# ADCHighVoltageInputsSchDoc.net
KiCad netlist of a schematic drawn in Altium Designer
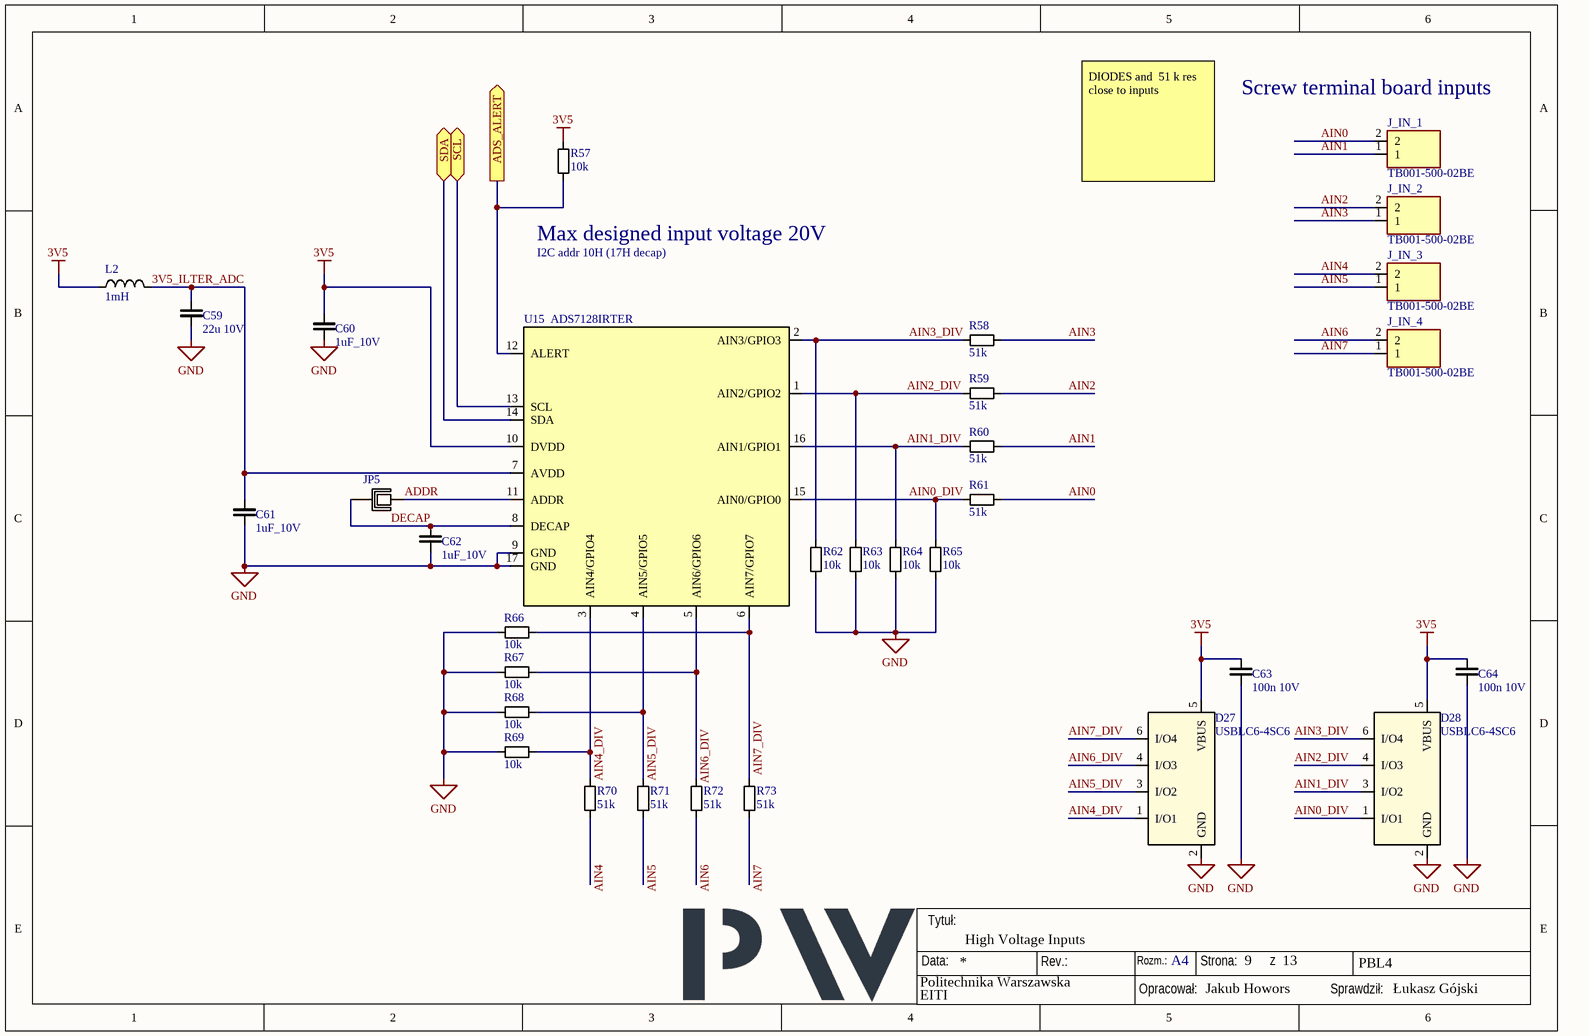
[diagram p0: ADCHighVoltageInputsSchDoc.SchDoc]

(export (version "E")
  (design (tool "Eeschema 10.0.6"))
  (components
    (comp (ref "C59")
      (value "22u 10V")
      (footprint "C_1206")
      (description "Ceramic capacitor")
      (fields (field (name "VOLTAGE") "10V") (field (name "TOLERANCE") "20%"))
      (libsource (lib "Common") (part "C_22uF_10V"))
    )
    (comp (ref "C60")
      (value "1uF_10V")
      (footprint "C_0603")
      (description "Ceramic capacitor")
      (fields (field (name "VOLTAGE") "10V") (field (name "TOLERANCE") "10%"))
      (libsource (lib "Common") (part "C_1uF_10V"))
    )
    (comp (ref "C61")
      (value "1uF_10V")
      (footprint "C_0603")
      (description "Ceramic capacitor")
      (fields (field (name "VOLTAGE") "10V") (field (name "TOLERANCE") "10%"))
      (libsource (lib "Common") (part "C_1uF_10V"))
    )
    (comp (ref "C62")
      (value "1uF_10V")
      (footprint "C_0603")
      (description "Ceramic capacitor")
      (fields (field (name "VOLTAGE") "10V") (field (name "TOLERANCE") "10%"))
      (libsource (lib "Common") (part "C_1uF_10V"))
    )
    (comp (ref "C63")
      (value "100n 10V")
      (footprint "C_0603")
      (description "Ceramic capacitor")
      (fields (field (name "VOLTAGE") "10V") (field (name "TOLERANCE") "10%"))
      (libsource (lib "Common") (part "C_100nF_10V"))
    )
    (comp (ref "C64")
      (value "100n 10V")
      (footprint "C_0603")
      (description "Ceramic capacitor")
      (fields (field (name "VOLTAGE") "10V") (field (name "TOLERANCE") "10%"))
      (libsource (lib "Common") (part "C_100nF_10V"))
    )
    (comp (ref "D27")
      (value "USBLC6-4SC6")
      (footprint "SOT23-6L_STM")
      (description "Very low capacitance ESD protection")
      (fields (field (name "MANUFACTURER") "STMicroelectronics"))
      (libsource (lib "Common") (part "USBLC6-4SC6"))
    )
    (comp (ref "D28")
      (value "USBLC6-4SC6")
      (footprint "SOT23-6L_STM")
      (description "Very low capacitance ESD protection")
      (fields (field (name "MANUFACTURER") "STMicroelectronics"))
      (libsource (lib "Common") (part "USBLC6-4SC6"))
    )
    (comp (ref "JP5")
      (value "JUMPER")
      (footprint "Jumper")
      (description "Jumper on traces")
      (libsource (lib "Common") (part "Jumper x2"))
    )
    (comp (ref "J_IN_1")
      (value "TB001-500-02BE")
      (footprint "TB00150002BE")
      (description "Screw terminal x2 5mm spacing")
      (fields (field (name "MANUFACTURER") "Same Sky"))
      (libsource (lib "Common") (part "Screw Terminal x2 5mm"))
    )
    (comp (ref "J_IN_2")
      (value "TB001-500-02BE")
      (footprint "TB00150002BE")
      (description "Screw terminal x2 5mm spacing")
      (fields (field (name "MANUFACTURER") "Same Sky"))
      (libsource (lib "Common") (part "Screw Terminal x2 5mm"))
    )
    (comp (ref "J_IN_3")
      (value "TB001-500-02BE")
      (footprint "TB00150002BE")
      (description "Screw terminal x2 5mm spacing")
      (fields (field (name "MANUFACTURER") "Same Sky"))
      (libsource (lib "Common") (part "Screw Terminal x2 5mm"))
    )
    (comp (ref "J_IN_4")
      (value "TB001-500-02BE")
      (footprint "TB00150002BE")
      (description "Screw terminal x2 5mm spacing")
      (fields (field (name "MANUFACTURER") "Same Sky"))
      (libsource (lib "Common") (part "Screw Terminal x2 5mm"))
    )
    (comp (ref "L2")
      (value "1mH")
      (footprint "L_1007")
      (description "Inductor")
      (fields (field (name "TOLERANCE") "20%"))
      (libsource (lib "IOLib") (part "L_1mH"))
    )
    (comp (ref "R57")
      (value "10k")
      (footprint "R_0603")
      (description "Resistor")
      (fields (field (name "TOLERANCE") "1%") (field (name "POWER") "100mW"))
      (libsource (lib "Common") (part "R_10k"))
    )
    (comp (ref "R58")
      (value "51k")
      (footprint "R_0603")
      (fields (field (name "TOLERANCE") "0.1%") (field (name "POWER") "100mW"))
      (libsource (lib "IOLib") (part "R_51k_LT"))
    )
    (comp (ref "R59")
      (value "51k")
      (footprint "R_0603")
      (fields (field (name "TOLERANCE") "0.1%") (field (name "POWER") "100mW"))
      (libsource (lib "IOLib") (part "R_51k_LT"))
    )
    (comp (ref "R60")
      (value "51k")
      (footprint "R_0603")
      (fields (field (name "TOLERANCE") "0.1%") (field (name "POWER") "100mW"))
      (libsource (lib "IOLib") (part "R_51k_LT"))
    )
    (comp (ref "R61")
      (value "51k")
      (footprint "R_0603")
      (fields (field (name "TOLERANCE") "0.1%") (field (name "POWER") "100mW"))
      (libsource (lib "IOLib") (part "R_51k_LT"))
    )
    (comp (ref "R62")
      (value "10k")
      (footprint "R_0603")
      (fields (field (name "TOLERANCE") "0.1%") (field (name "POWER") "125mW"))
      (libsource (lib "IOLib") (part "R_10k_LT"))
    )
    (comp (ref "R63")
      (value "10k")
      (footprint "R_0603")
      (fields (field (name "TOLERANCE") "0.1%") (field (name "POWER") "125mW"))
      (libsource (lib "IOLib") (part "R_10k_LT"))
    )
    (comp (ref "R64")
      (value "10k")
      (footprint "R_0603")
      (fields (field (name "TOLERANCE") "0.1%") (field (name "POWER") "125mW"))
      (libsource (lib "IOLib") (part "R_10k_LT"))
    )
    (comp (ref "R65")
      (value "10k")
      (footprint "R_0603")
      (fields (field (name "TOLERANCE") "0.1%") (field (name "POWER") "125mW"))
      (libsource (lib "IOLib") (part "R_10k_LT"))
    )
    (comp (ref "R66")
      (value "10k")
      (footprint "R_0603")
      (fields (field (name "TOLERANCE") "0.1%") (field (name "POWER") "125mW"))
      (libsource (lib "IOLib") (part "R_10k_LT"))
    )
    (comp (ref "R67")
      (value "10k")
      (footprint "R_0603")
      (fields (field (name "TOLERANCE") "0.1%") (field (name "POWER") "125mW"))
      (libsource (lib "IOLib") (part "R_10k_LT"))
    )
    (comp (ref "R68")
      (value "10k")
      (footprint "R_0603")
      (fields (field (name "TOLERANCE") "0.1%") (field (name "POWER") "125mW"))
      (libsource (lib "IOLib") (part "R_10k_LT"))
    )
    (comp (ref "R69")
      (value "10k")
      (footprint "R_0603")
      (fields (field (name "TOLERANCE") "0.1%") (field (name "POWER") "125mW"))
      (libsource (lib "IOLib") (part "R_10k_LT"))
    )
    (comp (ref "R70")
      (value "51k")
      (footprint "R_0603")
      (fields (field (name "TOLERANCE") "0.1%") (field (name "POWER") "100mW"))
      (libsource (lib "IOLib") (part "R_51k_LT"))
    )
    (comp (ref "R71")
      (value "51k")
      (footprint "R_0603")
      (fields (field (name "TOLERANCE") "0.1%") (field (name "POWER") "100mW"))
      (libsource (lib "IOLib") (part "R_51k_LT"))
    )
    (comp (ref "R72")
      (value "51k")
      (footprint "R_0603")
      (fields (field (name "TOLERANCE") "0.1%") (field (name "POWER") "100mW"))
      (libsource (lib "IOLib") (part "R_51k_LT"))
    )
    (comp (ref "R73")
      (value "51k")
      (footprint "R_0603")
      (fields (field (name "TOLERANCE") "0.1%") (field (name "POWER") "100mW"))
      (libsource (lib "IOLib") (part "R_51k_LT"))
    )
    (comp (ref "U15")
      (value "ADS7128IRTER")
      (footprint "ADS7128_RTE0016C")
      (fields (field (name "COPYRIGHT") "Copyright (C) 2026 Ultra Librarian. All rights reserved."))
      (libsource (lib "IOLib") (part "IC_ads7128_ADS7128IRTER"))
    )
  )
  (nets
    (net (code "1") (name "/3V5_ILTER_ADC") (class "Default")
      (node (ref "C59") (pin "2") (pinfunction "2_2") (pintype "passive"))
      (node (ref "C61") (pin "2") (pinfunction "2_2") (pintype "passive"))
      (node (ref "L2") (pin "2") (pinfunction "2_2") (pintype "passive"))
      (node (ref "U15") (pin "7") (pinfunction "AVDD_7") (pintype "passive"))
    )
    (net (code "3") (name "/ADDR") (class "Default")
      (node (ref "JP5") (pin "1") (pinfunction "1_1") (pintype "passive"))
      (node (ref "U15") (pin "11") (pinfunction "ADDR_11") (pintype "passive"))
    )
    (net (code "4") (name "/ADS_ALERT") (class "Default")
      (node (ref "R57") (pin "1") (pinfunction "1_1") (pintype "passive"))
      (node (ref "U15") (pin "12") (pinfunction "ALERT_12") (pintype "passive"))
    )
    (net (code "5") (name "/AIN0") (class "Default")
      (node (ref "J_IN_1") (pin "2") (pinfunction "2_2") (pintype "passive"))
      (node (ref "R61") (pin "2") (pinfunction "2_2") (pintype "passive"))
    )
    (net (code "6") (name "/AIN0_DIV") (class "Default")
      (node (ref "D28") (pin "1") (pinfunction "I/O1_1") (pintype "passive"))
      (node (ref "R61") (pin "1") (pinfunction "1_1") (pintype "passive"))
      (node (ref "R65") (pin "1") (pinfunction "1_1") (pintype "passive"))
      (node (ref "U15") (pin "15") (pinfunction "AIN0/GPIO0_15") (pintype "passive"))
    )
    (net (code "7") (name "/AIN1") (class "Default")
      (node (ref "J_IN_1") (pin "1") (pinfunction "1_1") (pintype "passive"))
      (node (ref "R60") (pin "2") (pinfunction "2_2") (pintype "passive"))
    )
    (net (code "8") (name "/AIN1_DIV") (class "Default")
      (node (ref "D28") (pin "3") (pinfunction "I/O2_3") (pintype "passive"))
      (node (ref "R60") (pin "1") (pinfunction "1_1") (pintype "passive"))
      (node (ref "R64") (pin "1") (pinfunction "1_1") (pintype "passive"))
      (node (ref "U15") (pin "16") (pinfunction "AIN1/GPIO1_16") (pintype "passive"))
    )
    (net (code "9") (name "/AIN2") (class "Default")
      (node (ref "J_IN_2") (pin "2") (pinfunction "2_2") (pintype "passive"))
      (node (ref "R59") (pin "2") (pinfunction "2_2") (pintype "passive"))
    )
    (net (code "10") (name "/AIN2_DIV") (class "Default")
      (node (ref "D28") (pin "4") (pinfunction "I/O3_4") (pintype "passive"))
      (node (ref "R59") (pin "1") (pinfunction "1_1") (pintype "passive"))
      (node (ref "R63") (pin "1") (pinfunction "1_1") (pintype "passive"))
      (node (ref "U15") (pin "1") (pinfunction "AIN2/GPIO2_1") (pintype "passive"))
    )
    (net (code "11") (name "/AIN3") (class "Default")
      (node (ref "J_IN_2") (pin "1") (pinfunction "1_1") (pintype "passive"))
      (node (ref "R58") (pin "2") (pinfunction "2_2") (pintype "passive"))
    )
    (net (code "12") (name "/AIN3_DIV") (class "Default")
      (node (ref "D28") (pin "6") (pinfunction "I/O4_6") (pintype "passive"))
      (node (ref "R58") (pin "1") (pinfunction "1_1") (pintype "passive"))
      (node (ref "R62") (pin "1") (pinfunction "1_1") (pintype "passive"))
      (node (ref "U15") (pin "2") (pinfunction "AIN3/GPIO3_2") (pintype "passive"))
    )
    (net (code "13") (name "/AIN4") (class "Default")
      (node (ref "J_IN_3") (pin "2") (pinfunction "2_2") (pintype "passive"))
      (node (ref "R70") (pin "2") (pinfunction "2_2") (pintype "passive"))
    )
    (net (code "14") (name "/AIN4_DIV") (class "Default")
      (node (ref "D27") (pin "1") (pinfunction "I/O1_1") (pintype "passive"))
      (node (ref "R69") (pin "1") (pinfunction "1_1") (pintype "passive"))
      (node (ref "R70") (pin "1") (pinfunction "1_1") (pintype "passive"))
      (node (ref "U15") (pin "3") (pinfunction "AIN4/GPIO4_3") (pintype "passive"))
    )
    (net (code "15") (name "/AIN5") (class "Default")
      (node (ref "J_IN_3") (pin "1") (pinfunction "1_1") (pintype "passive"))
      (node (ref "R71") (pin "2") (pinfunction "2_2") (pintype "passive"))
    )
    (net (code "16") (name "/AIN5_DIV") (class "Default")
      (node (ref "D27") (pin "3") (pinfunction "I/O2_3") (pintype "passive"))
      (node (ref "R68") (pin "1") (pinfunction "1_1") (pintype "passive"))
      (node (ref "R71") (pin "1") (pinfunction "1_1") (pintype "passive"))
      (node (ref "U15") (pin "4") (pinfunction "AIN5/GPIO5_4") (pintype "passive"))
    )
    (net (code "17") (name "/AIN6") (class "Default")
      (node (ref "J_IN_4") (pin "2") (pinfunction "2_2") (pintype "passive"))
      (node (ref "R72") (pin "2") (pinfunction "2_2") (pintype "passive"))
    )
    (net (code "18") (name "/AIN6_DIV") (class "Default")
      (node (ref "D27") (pin "4") (pinfunction "I/O3_4") (pintype "passive"))
      (node (ref "R67") (pin "1") (pinfunction "1_1") (pintype "passive"))
      (node (ref "R72") (pin "1") (pinfunction "1_1") (pintype "passive"))
      (node (ref "U15") (pin "5") (pinfunction "AIN6/GPIO6_5") (pintype "passive"))
    )
    (net (code "19") (name "/AIN7") (class "Default")
      (node (ref "J_IN_4") (pin "1") (pinfunction "1_1") (pintype "passive"))
      (node (ref "R73") (pin "2") (pinfunction "2_2") (pintype "passive"))
    )
    (net (code "20") (name "/AIN7_DIV") (class "Default")
      (node (ref "D27") (pin "6") (pinfunction "I/O4_6") (pintype "passive"))
      (node (ref "R66") (pin "1") (pinfunction "1_1") (pintype "passive"))
      (node (ref "R73") (pin "1") (pinfunction "1_1") (pintype "passive"))
      (node (ref "U15") (pin "6") (pinfunction "AIN7/GPIO7_6") (pintype "passive"))
    )
    (net (code "21") (name "/DECAP") (class "Default")
      (node (ref "C62") (pin "2") (pinfunction "2_2") (pintype "passive"))
      (node (ref "JP5") (pin "2") (pinfunction "2_2") (pintype "passive"))
      (node (ref "U15") (pin "8") (pinfunction "DECAP_8") (pintype "passive"))
    )
    (net (code "22") (name "/SCL") (class "Default")
      (node (ref "U15") (pin "13") (pinfunction "SCL_13") (pintype "passive"))
    )
    (net (code "23") (name "/SDA") (class "Default")
      (node (ref "U15") (pin "14") (pinfunction "SDA_14") (pintype "passive"))
    )
    (net (code "24") (name "3V5") (class "Default")
      (node (ref "C60") (pin "2") (pinfunction "2_2") (pintype "passive"))
      (node (ref "C63") (pin "2") (pinfunction "2_2") (pintype "passive"))
      (node (ref "C64") (pin "2") (pinfunction "2_2") (pintype "passive"))
      (node (ref "D27") (pin "5") (pinfunction "VBUS_5") (pintype "passive"))
      (node (ref "D28") (pin "5") (pinfunction "VBUS_5") (pintype "passive"))
      (node (ref "L2") (pin "1") (pinfunction "1_1") (pintype "passive"))
      (node (ref "R57") (pin "2") (pinfunction "2_2") (pintype "passive"))
      (node (ref "U15") (pin "10") (pinfunction "DVDD_10") (pintype "passive"))
    )
    (net (code "25") (name "GND") (class "Default")
      (node (ref "C59") (pin "1") (pinfunction "1_1") (pintype "passive"))
      (node (ref "C60") (pin "1") (pinfunction "1_1") (pintype "passive"))
      (node (ref "C61") (pin "1") (pinfunction "1_1") (pintype "passive"))
      (node (ref "C62") (pin "1") (pinfunction "1_1") (pintype "passive"))
      (node (ref "C63") (pin "1") (pinfunction "1_1") (pintype "passive"))
      (node (ref "C64") (pin "1") (pinfunction "1_1") (pintype "passive"))
      (node (ref "D27") (pin "2") (pinfunction "GND_2") (pintype "passive"))
      (node (ref "D28") (pin "2") (pinfunction "GND_2") (pintype "passive"))
      (node (ref "R62") (pin "2") (pinfunction "2_2") (pintype "passive"))
      (node (ref "R63") (pin "2") (pinfunction "2_2") (pintype "passive"))
      (node (ref "R64") (pin "2") (pinfunction "2_2") (pintype "passive"))
      (node (ref "R65") (pin "2") (pinfunction "2_2") (pintype "passive"))
      (node (ref "R66") (pin "2") (pinfunction "2_2") (pintype "passive"))
      (node (ref "R67") (pin "2") (pinfunction "2_2") (pintype "passive"))
      (node (ref "R68") (pin "2") (pinfunction "2_2") (pintype "passive"))
      (node (ref "R69") (pin "2") (pinfunction "2_2") (pintype "passive"))
      (node (ref "U15") (pin "17") (pinfunction "GND_17") (pintype "passive"))
      (node (ref "U15") (pin "9") (pinfunction "GND_9") (pintype "passive"))
    )
  )
)
